# MODULE_STRAPS_SAIL.net
KiCad netlist of a schematic drawn in Altium Designer
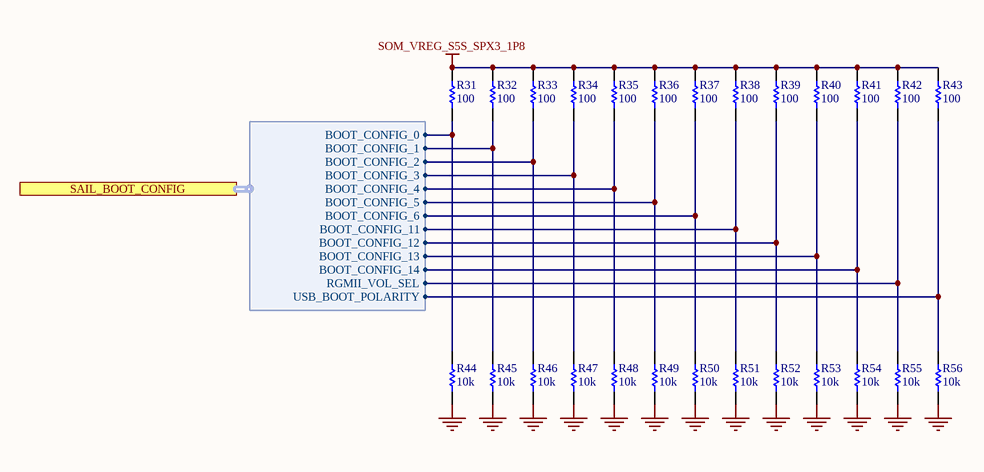
[diagram p0: MODULE_STRAPS_SAIL.SchDoc]

(export (version "E")
  (design (tool "Eeschema 10.0.6"))
  (components
    (comp (ref "R31")
      (value "100")
      (footprint "RES-0201")
      (description "RES CHIP 0201 100R 1% 1/20W")
      (fields (field (name "POWER") "50mW") (field (name "TOLERANCE") "1%"))
      (libsource (lib "Clean") (part "RES"))
    )
    (comp (ref "R32")
      (value "100")
      (footprint "RES-0201")
      (description "RES CHIP 0201 100R 1% 1/20W")
      (fields (field (name "POWER") "50mW") (field (name "TOLERANCE") "1%"))
      (libsource (lib "Clean") (part "RES"))
    )
    (comp (ref "R33")
      (value "100")
      (footprint "RES-0201")
      (description "RES CHIP 0201 100R 1% 1/20W")
      (fields (field (name "POWER") "50mW") (field (name "TOLERANCE") "1%"))
      (libsource (lib "Clean") (part "RES"))
    )
    (comp (ref "R34")
      (value "100")
      (footprint "RES-0201")
      (description "RES CHIP 0201 100R 1% 1/20W")
      (fields (field (name "POWER") "50mW") (field (name "TOLERANCE") "1%"))
      (libsource (lib "Clean") (part "RES"))
    )
    (comp (ref "R35")
      (value "100")
      (footprint "RES-0201")
      (description "RES CHIP 0201 100R 1% 1/20W")
      (fields (field (name "POWER") "50mW") (field (name "TOLERANCE") "1%"))
      (libsource (lib "Clean") (part "RES"))
    )
    (comp (ref "R36")
      (value "100")
      (footprint "RES-0201")
      (description "RES CHIP 0201 100R 1% 1/20W")
      (fields (field (name "POWER") "50mW") (field (name "TOLERANCE") "1%"))
      (libsource (lib "Clean") (part "RES"))
    )
    (comp (ref "R37")
      (value "100")
      (footprint "RES-0201")
      (description "RES CHIP 0201 100R 1% 1/20W")
      (fields (field (name "POWER") "50mW") (field (name "TOLERANCE") "1%"))
      (libsource (lib "Clean") (part "RES"))
    )
    (comp (ref "R38")
      (value "100")
      (footprint "RES-0201")
      (description "RES CHIP 0201 100R 1% 1/20W")
      (fields (field (name "POWER") "50mW") (field (name "TOLERANCE") "1%"))
      (libsource (lib "Clean") (part "RES"))
    )
    (comp (ref "R39")
      (value "100")
      (footprint "RES-0201")
      (description "RES CHIP 0201 100R 1% 1/20W")
      (fields (field (name "POWER") "50mW") (field (name "TOLERANCE") "1%"))
      (libsource (lib "Clean") (part "RES"))
    )
    (comp (ref "R40")
      (value "100")
      (footprint "RES-0201")
      (description "RES CHIP 0201 100R 1% 1/20W")
      (fields (field (name "POWER") "50mW") (field (name "TOLERANCE") "1%"))
      (libsource (lib "Clean") (part "RES"))
    )
    (comp (ref "R41")
      (value "100")
      (footprint "RES-0201")
      (description "RES CHIP 0201 100R 1% 1/20W")
      (fields (field (name "POWER") "50mW") (field (name "TOLERANCE") "1%"))
      (libsource (lib "Clean") (part "RES"))
    )
    (comp (ref "R42")
      (value "100")
      (footprint "RES-0201")
      (description "RES CHIP 0201 100R 1% 1/20W")
      (fields (field (name "POWER") "50mW") (field (name "TOLERANCE") "1%"))
      (libsource (lib "Clean") (part "RES"))
    )
    (comp (ref "R43")
      (value "100")
      (footprint "RES-0201")
      (description "RES CHIP 0201 100R 1% 1/20W")
      (fields (field (name "POWER") "50mW") (field (name "TOLERANCE") "1%"))
      (libsource (lib "Clean") (part "RES"))
    )
    (comp (ref "R44")
      (value "10k")
      (footprint "RES-0201")
      (description "RES CHIP 0201 10k 1% 1/20W")
      (fields (field (name "POWER") "50mW") (field (name "TOLERANCE") "1%"))
      (libsource (lib "Clean") (part "RES"))
    )
    (comp (ref "R45")
      (value "10k")
      (footprint "RES-0201")
      (description "RES CHIP 0201 10k 1% 1/20W")
      (fields (field (name "POWER") "50mW") (field (name "TOLERANCE") "1%"))
      (libsource (lib "Clean") (part "RES"))
    )
    (comp (ref "R46")
      (value "10k")
      (footprint "RES-0201")
      (description "RES CHIP 0201 10k 1% 1/20W")
      (fields (field (name "POWER") "50mW") (field (name "TOLERANCE") "1%"))
      (libsource (lib "Clean") (part "RES"))
    )
    (comp (ref "R47")
      (value "10k")
      (footprint "RES-0201")
      (description "RES CHIP 0201 10k 1% 1/20W")
      (fields (field (name "POWER") "50mW") (field (name "TOLERANCE") "1%"))
      (libsource (lib "Clean") (part "RES"))
    )
    (comp (ref "R48")
      (value "10k")
      (footprint "RES-0201")
      (description "RES CHIP 0201 10k 1% 1/20W")
      (fields (field (name "POWER") "50mW") (field (name "TOLERANCE") "1%"))
      (libsource (lib "Clean") (part "RES"))
    )
    (comp (ref "R49")
      (value "10k")
      (footprint "RES-0201")
      (description "RES CHIP 0201 10k 1% 1/20W")
      (fields (field (name "POWER") "50mW") (field (name "TOLERANCE") "1%"))
      (libsource (lib "Clean") (part "RES"))
    )
    (comp (ref "R50")
      (value "10k")
      (footprint "RES-0201")
      (description "RES CHIP 0201 10k 1% 1/20W")
      (fields (field (name "POWER") "50mW") (field (name "TOLERANCE") "1%"))
      (libsource (lib "Clean") (part "RES"))
    )
    (comp (ref "R51")
      (value "10k")
      (footprint "RES-0201")
      (description "RES CHIP 0201 10k 1% 1/20W")
      (fields (field (name "POWER") "50mW") (field (name "TOLERANCE") "1%"))
      (libsource (lib "Clean") (part "RES"))
    )
    (comp (ref "R52")
      (value "10k")
      (footprint "RES-0201")
      (description "RES CHIP 0201 10k 1% 1/20W")
      (fields (field (name "POWER") "50mW") (field (name "TOLERANCE") "1%"))
      (libsource (lib "Clean") (part "RES"))
    )
    (comp (ref "R53")
      (value "10k")
      (footprint "RES-0201")
      (description "RES CHIP 0201 10k 1% 1/20W")
      (fields (field (name "POWER") "50mW") (field (name "TOLERANCE") "1%"))
      (libsource (lib "Clean") (part "RES"))
    )
    (comp (ref "R54")
      (value "10k")
      (footprint "RES-0201")
      (description "RES CHIP 0201 10k 1% 1/20W")
      (fields (field (name "POWER") "50mW") (field (name "TOLERANCE") "1%"))
      (libsource (lib "Clean") (part "RES"))
    )
    (comp (ref "R55")
      (value "10k")
      (footprint "RES-0201")
      (description "RES CHIP 0201 10k 1% 1/20W")
      (fields (field (name "POWER") "50mW") (field (name "TOLERANCE") "1%"))
      (libsource (lib "Clean") (part "RES"))
    )
    (comp (ref "R56")
      (value "10k")
      (footprint "RES-0201")
      (description "RES CHIP 0201 10k 1% 1/20W")
      (fields (field (name "POWER") "50mW") (field (name "TOLERANCE") "1%"))
      (libsource (lib "Clean") (part "RES"))
    )
  )
  (nets
    (net (code "3") (name "GND") (class "Default")
      (node (ref "R44") (pin "1") (pinfunction "1_1") (pintype "passive"))
      (node (ref "R45") (pin "1") (pinfunction "1_1") (pintype "passive"))
      (node (ref "R46") (pin "1") (pinfunction "1_1") (pintype "passive"))
      (node (ref "R47") (pin "1") (pinfunction "1_1") (pintype "passive"))
      (node (ref "R48") (pin "1") (pinfunction "1_1") (pintype "passive"))
      (node (ref "R49") (pin "1") (pinfunction "1_1") (pintype "passive"))
      (node (ref "R50") (pin "1") (pinfunction "1_1") (pintype "passive"))
      (node (ref "R51") (pin "1") (pinfunction "1_1") (pintype "passive"))
      (node (ref "R52") (pin "1") (pinfunction "1_1") (pintype "passive"))
      (node (ref "R53") (pin "1") (pinfunction "1_1") (pintype "passive"))
      (node (ref "R54") (pin "1") (pinfunction "1_1") (pintype "passive"))
      (node (ref "R55") (pin "1") (pinfunction "1_1") (pintype "passive"))
      (node (ref "R56") (pin "1") (pinfunction "1_1") (pintype "passive"))
    )
    (net (code "4") (name "Net-(R31-Pad2)") (class "Default")
      (node (ref "R31") (pin "2") (pinfunction "2_2") (pintype "passive"))
      (node (ref "R44") (pin "2") (pinfunction "2_2") (pintype "passive"))
    )
    (net (code "5") (name "Net-(R32-Pad2)") (class "Default")
      (node (ref "R32") (pin "2") (pinfunction "2_2") (pintype "passive"))
      (node (ref "R45") (pin "2") (pinfunction "2_2") (pintype "passive"))
    )
    (net (code "6") (name "Net-(R33-Pad2)") (class "Default")
      (node (ref "R33") (pin "2") (pinfunction "2_2") (pintype "passive"))
      (node (ref "R46") (pin "2") (pinfunction "2_2") (pintype "passive"))
    )
    (net (code "7") (name "Net-(R34-Pad2)") (class "Default")
      (node (ref "R34") (pin "2") (pinfunction "2_2") (pintype "passive"))
      (node (ref "R47") (pin "2") (pinfunction "2_2") (pintype "passive"))
    )
    (net (code "8") (name "Net-(R35-Pad2)") (class "Default")
      (node (ref "R35") (pin "2") (pinfunction "2_2") (pintype "passive"))
      (node (ref "R48") (pin "2") (pinfunction "2_2") (pintype "passive"))
    )
    (net (code "9") (name "Net-(R36-Pad2)") (class "Default")
      (node (ref "R36") (pin "2") (pinfunction "2_2") (pintype "passive"))
      (node (ref "R49") (pin "2") (pinfunction "2_2") (pintype "passive"))
    )
    (net (code "10") (name "Net-(R37-Pad2)") (class "Default")
      (node (ref "R37") (pin "2") (pinfunction "2_2") (pintype "passive"))
      (node (ref "R50") (pin "2") (pinfunction "2_2") (pintype "passive"))
    )
    (net (code "11") (name "Net-(R38-Pad2)") (class "Default")
      (node (ref "R38") (pin "2") (pinfunction "2_2") (pintype "passive"))
      (node (ref "R51") (pin "2") (pinfunction "2_2") (pintype "passive"))
    )
    (net (code "12") (name "Net-(R39-Pad2)") (class "Default")
      (node (ref "R39") (pin "2") (pinfunction "2_2") (pintype "passive"))
      (node (ref "R52") (pin "2") (pinfunction "2_2") (pintype "passive"))
    )
    (net (code "13") (name "Net-(R40-Pad2)") (class "Default")
      (node (ref "R40") (pin "2") (pinfunction "2_2") (pintype "passive"))
      (node (ref "R53") (pin "2") (pinfunction "2_2") (pintype "passive"))
    )
    (net (code "14") (name "Net-(R41-Pad2)") (class "Default")
      (node (ref "R41") (pin "2") (pinfunction "2_2") (pintype "passive"))
      (node (ref "R54") (pin "2") (pinfunction "2_2") (pintype "passive"))
    )
    (net (code "15") (name "Net-(R42-Pad2)") (class "Default")
      (node (ref "R42") (pin "2") (pinfunction "2_2") (pintype "passive"))
      (node (ref "R55") (pin "2") (pinfunction "2_2") (pintype "passive"))
    )
    (net (code "16") (name "Net-(R43-Pad2)") (class "Default")
      (node (ref "R43") (pin "2") (pinfunction "2_2") (pintype "passive"))
      (node (ref "R56") (pin "2") (pinfunction "2_2") (pintype "passive"))
    )
    (net (code "17") (name "SOM_VREG_S5S_SPX3_1P8") (class "Default")
      (node (ref "R31") (pin "1") (pinfunction "1_1") (pintype "passive"))
      (node (ref "R32") (pin "1") (pinfunction "1_1") (pintype "passive"))
      (node (ref "R33") (pin "1") (pinfunction "1_1") (pintype "passive"))
      (node (ref "R34") (pin "1") (pinfunction "1_1") (pintype "passive"))
      (node (ref "R35") (pin "1") (pinfunction "1_1") (pintype "passive"))
      (node (ref "R36") (pin "1") (pinfunction "1_1") (pintype "passive"))
      (node (ref "R37") (pin "1") (pinfunction "1_1") (pintype "passive"))
      (node (ref "R38") (pin "1") (pinfunction "1_1") (pintype "passive"))
      (node (ref "R39") (pin "1") (pinfunction "1_1") (pintype "passive"))
      (node (ref "R40") (pin "1") (pinfunction "1_1") (pintype "passive"))
      (node (ref "R41") (pin "1") (pinfunction "1_1") (pintype "passive"))
      (node (ref "R42") (pin "1") (pinfunction "1_1") (pintype "passive"))
      (node (ref "R43") (pin "1") (pinfunction "1_1") (pintype "passive"))
    )
  )
)
